# Safety_Thermocouple_Interface_-_IO.net
KiCad netlist of a schematic drawn in Altium Designer
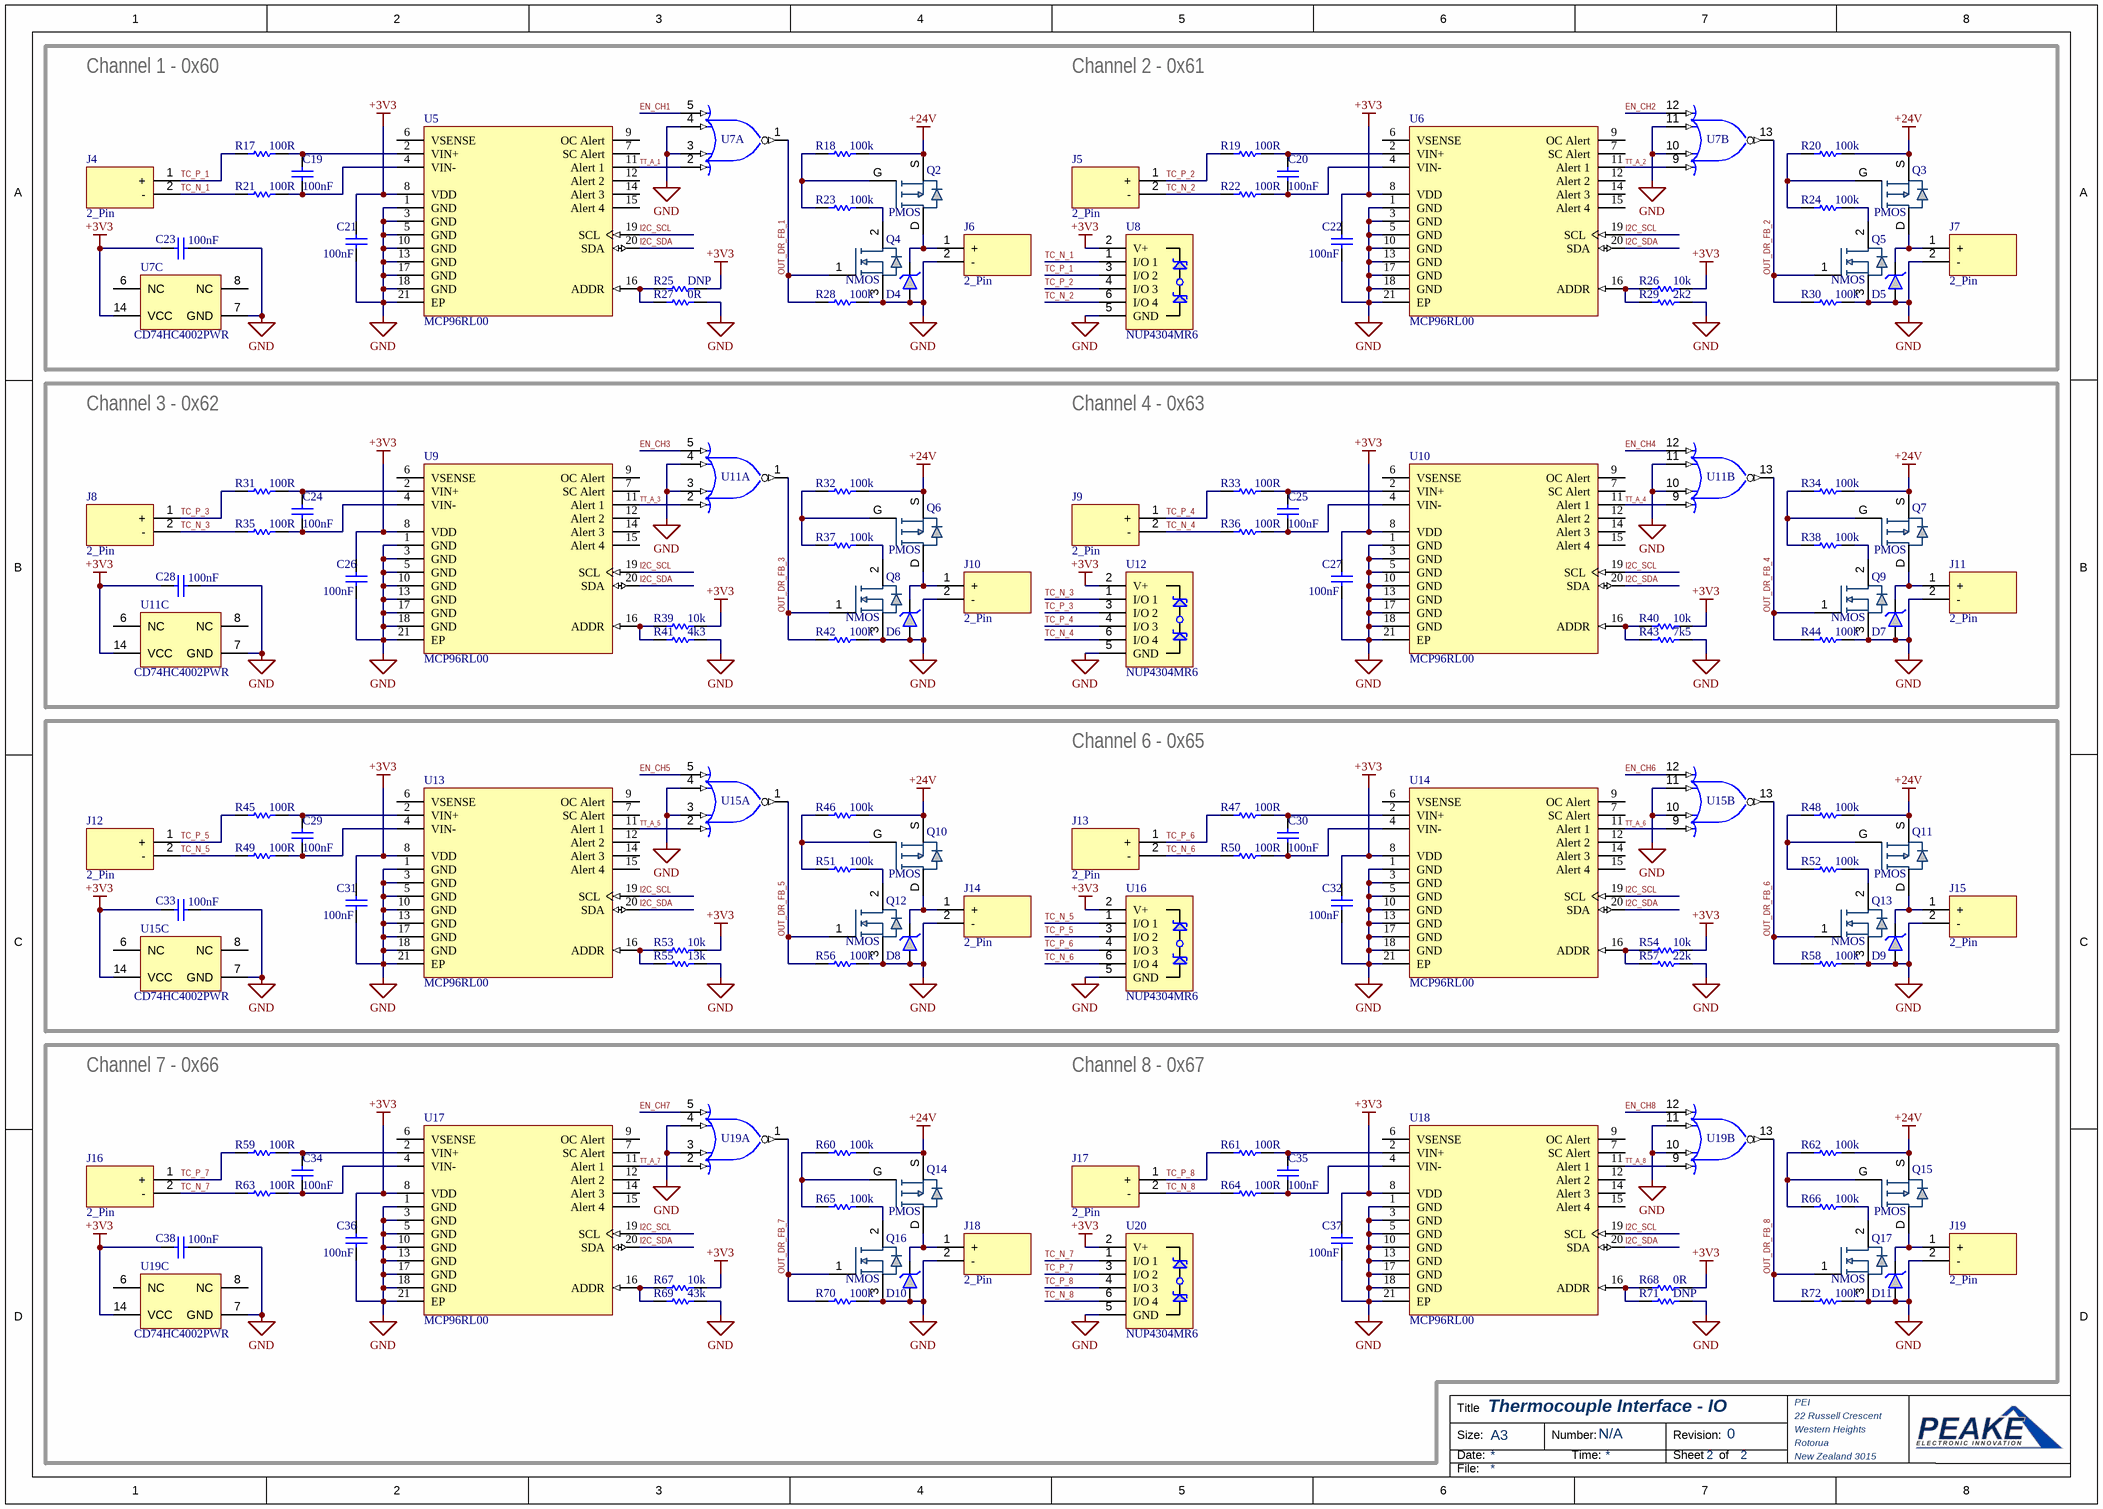
[diagram p0: Safety Thermocouple Interface - IO.SchDoc]

(export (version "E")
  (design (tool "Eeschema 10.0.6"))
  (components
    (comp (ref "C19")
      (value "100nF")
      (footprint "0603_CAP")
      (description "SMD Capacitor")
      (fields (field (name "Comment") "Capacitor"))
      (libsource (lib "Scion Research") (part "CMP-019-00005-2"))
    )
    (comp (ref "C20")
      (value "100nF")
      (footprint "0603_CAP")
      (description "SMD Capacitor")
      (fields (field (name "Comment") "Capacitor"))
      (libsource (lib "Scion Research") (part "CMP-019-00005-2"))
    )
    (comp (ref "C21")
      (value "100nF")
      (footprint "0603_CAP")
      (description "SMD Capacitor")
      (fields (field (name "Comment") "Capacitor"))
      (libsource (lib "Scion Research") (part "CMP-019-00005-2"))
    )
    (comp (ref "C22")
      (value "100nF")
      (footprint "0603_CAP")
      (description "SMD Capacitor")
      (fields (field (name "Comment") "Capacitor"))
      (libsource (lib "Scion Research") (part "CMP-019-00005-2"))
    )
    (comp (ref "C23")
      (value "100nF")
      (footprint "0603_CAP")
      (description "SMD Capacitor")
      (fields (field (name "Comment") "Capacitor"))
      (libsource (lib "Scion Research") (part "CMP-019-00005-2"))
    )
    (comp (ref "C24")
      (value "100nF")
      (footprint "0603_CAP")
      (description "SMD Capacitor")
      (fields (field (name "Comment") "Capacitor"))
      (libsource (lib "Scion Research") (part "CMP-019-00005-2"))
    )
    (comp (ref "C25")
      (value "100nF")
      (footprint "0603_CAP")
      (description "SMD Capacitor")
      (fields (field (name "Comment") "Capacitor"))
      (libsource (lib "Scion Research") (part "CMP-019-00005-2"))
    )
    (comp (ref "C26")
      (value "100nF")
      (footprint "0603_CAP")
      (description "SMD Capacitor")
      (fields (field (name "Comment") "Capacitor"))
      (libsource (lib "Scion Research") (part "CMP-019-00005-2"))
    )
    (comp (ref "C27")
      (value "100nF")
      (footprint "0603_CAP")
      (description "SMD Capacitor")
      (fields (field (name "Comment") "Capacitor"))
      (libsource (lib "Scion Research") (part "CMP-019-00005-2"))
    )
    (comp (ref "C28")
      (value "100nF")
      (footprint "0603_CAP")
      (description "SMD Capacitor")
      (fields (field (name "Comment") "Capacitor"))
      (libsource (lib "Scion Research") (part "CMP-019-00005-2"))
    )
    (comp (ref "C29")
      (value "100nF")
      (footprint "0603_CAP")
      (description "SMD Capacitor")
      (fields (field (name "Comment") "Capacitor"))
      (libsource (lib "Scion Research") (part "CMP-019-00005-2"))
    )
    (comp (ref "C30")
      (value "100nF")
      (footprint "0603_CAP")
      (description "SMD Capacitor")
      (fields (field (name "Comment") "Capacitor"))
      (libsource (lib "Scion Research") (part "CMP-019-00005-2"))
    )
    (comp (ref "C31")
      (value "100nF")
      (footprint "0603_CAP")
      (description "SMD Capacitor")
      (fields (field (name "Comment") "Capacitor"))
      (libsource (lib "Scion Research") (part "CMP-019-00005-2"))
    )
    (comp (ref "C32")
      (value "100nF")
      (footprint "0603_CAP")
      (description "SMD Capacitor")
      (fields (field (name "Comment") "Capacitor"))
      (libsource (lib "Scion Research") (part "CMP-019-00005-2"))
    )
    (comp (ref "C33")
      (value "100nF")
      (footprint "0603_CAP")
      (description "SMD Capacitor")
      (fields (field (name "Comment") "Capacitor"))
      (libsource (lib "Scion Research") (part "CMP-019-00005-2"))
    )
    (comp (ref "C34")
      (value "100nF")
      (footprint "0603_CAP")
      (description "SMD Capacitor")
      (fields (field (name "Comment") "Capacitor"))
      (libsource (lib "Scion Research") (part "CMP-019-00005-2"))
    )
    (comp (ref "C35")
      (value "100nF")
      (footprint "0603_CAP")
      (description "SMD Capacitor")
      (fields (field (name "Comment") "Capacitor"))
      (libsource (lib "Scion Research") (part "CMP-019-00005-2"))
    )
    (comp (ref "C36")
      (value "100nF")
      (footprint "0603_CAP")
      (description "SMD Capacitor")
      (fields (field (name "Comment") "Capacitor"))
      (libsource (lib "Scion Research") (part "CMP-019-00005-2"))
    )
    (comp (ref "C37")
      (value "100nF")
      (footprint "0603_CAP")
      (description "SMD Capacitor")
      (fields (field (name "Comment") "Capacitor"))
      (libsource (lib "Scion Research") (part "CMP-019-00005-2"))
    )
    (comp (ref "C38")
      (value "100nF")
      (footprint "0603_CAP")
      (description "SMD Capacitor")
      (fields (field (name "Comment") "Capacitor"))
      (libsource (lib "Scion Research") (part "CMP-019-00005-2"))
    )
    (comp (ref "D4")
      (value "Transil")
      (footprint "SMBJ")
      (description "Transient Voltage Suppressor")
      (libsource (lib "Scion Research") (part "CMP-004-0042-1"))
    )
    (comp (ref "D5")
      (value "Transil")
      (footprint "SMBJ")
      (description "Transient Voltage Suppressor")
      (libsource (lib "Scion Research") (part "CMP-004-0042-1"))
    )
    (comp (ref "D6")
      (value "Transil")
      (footprint "SMBJ")
      (description "Transient Voltage Suppressor")
      (libsource (lib "Scion Research") (part "CMP-004-0042-1"))
    )
    (comp (ref "D7")
      (value "Transil")
      (footprint "SMBJ")
      (description "Transient Voltage Suppressor")
      (libsource (lib "Scion Research") (part "CMP-004-0042-1"))
    )
    (comp (ref "D8")
      (value "Transil")
      (footprint "SMBJ")
      (description "Transient Voltage Suppressor")
      (libsource (lib "Scion Research") (part "CMP-004-0042-1"))
    )
    (comp (ref "D9")
      (value "Transil")
      (footprint "SMBJ")
      (description "Transient Voltage Suppressor")
      (libsource (lib "Scion Research") (part "CMP-004-0042-1"))
    )
    (comp (ref "D10")
      (value "Transil")
      (footprint "SMBJ")
      (description "Transient Voltage Suppressor")
      (libsource (lib "Scion Research") (part "CMP-004-0042-1"))
    )
    (comp (ref "D11")
      (value "Transil")
      (footprint "SMBJ")
      (description "Transient Voltage Suppressor")
      (libsource (lib "Scion Research") (part "CMP-004-0042-1"))
    )
    (comp (ref "J4")
      (value "2_Pin")
      (footprint "2_Pin DB2EVC-3.81-2P-GN")
      (description "2 Pin Connector")
      (libsource (lib "") (part "CMP-002-00074-8_1"))
    )
    (comp (ref "J5")
      (value "2_Pin")
      (footprint "2_Pin DB2EVC-3.81-2P-GN")
      (description "2 Pin Connector")
      (libsource (lib "") (part "CMP-002-00074-8_1"))
    )
    (comp (ref "J6")
      (value "2_Pin")
      (footprint "2_Pin DB2EVC-3.81-2P-GN")
      (description "2 Pin Connector")
      (libsource (lib "Scion Research") (part "CMP-002-00074-8"))
    )
    (comp (ref "J7")
      (value "2_Pin")
      (footprint "2_Pin DB2EVC-3.81-2P-GN")
      (description "2 Pin Connector")
      (libsource (lib "Scion Research") (part "CMP-002-00074-8"))
    )
    (comp (ref "J8")
      (value "2_Pin")
      (footprint "2_Pin DB2EVC-3.81-2P-GN")
      (description "2 Pin Connector")
      (libsource (lib "") (part "CMP-002-00074-8_1"))
    )
    (comp (ref "J9")
      (value "2_Pin")
      (footprint "2_Pin DB2EVC-3.81-2P-GN")
      (description "2 Pin Connector")
      (libsource (lib "") (part "CMP-002-00074-8_1"))
    )
    (comp (ref "J10")
      (value "2_Pin")
      (footprint "2_Pin DB2EVC-3.81-2P-GN")
      (description "2 Pin Connector")
      (libsource (lib "Scion Research") (part "CMP-002-00074-8"))
    )
    (comp (ref "J11")
      (value "2_Pin")
      (footprint "2_Pin DB2EVC-3.81-2P-GN")
      (description "2 Pin Connector")
      (libsource (lib "Scion Research") (part "CMP-002-00074-8"))
    )
    (comp (ref "J12")
      (value "2_Pin")
      (footprint "2_Pin DB2EVC-3.81-2P-GN")
      (description "2 Pin Connector")
      (libsource (lib "") (part "CMP-002-00074-8_1"))
    )
    (comp (ref "J13")
      (value "2_Pin")
      (footprint "2_Pin DB2EVC-3.81-2P-GN")
      (description "2 Pin Connector")
      (libsource (lib "") (part "CMP-002-00074-8_1"))
    )
    (comp (ref "J14")
      (value "2_Pin")
      (footprint "2_Pin DB2EVC-3.81-2P-GN")
      (description "2 Pin Connector")
      (libsource (lib "Scion Research") (part "CMP-002-00074-8"))
    )
    (comp (ref "J15")
      (value "2_Pin")
      (footprint "2_Pin DB2EVC-3.81-2P-GN")
      (description "2 Pin Connector")
      (libsource (lib "Scion Research") (part "CMP-002-00074-8"))
    )
    (comp (ref "J16")
      (value "2_Pin")
      (footprint "2_Pin DB2EVC-3.81-2P-GN")
      (description "2 Pin Connector")
      (libsource (lib "") (part "CMP-002-00074-8_1"))
    )
    (comp (ref "J17")
      (value "2_Pin")
      (footprint "2_Pin DB2EVC-3.81-2P-GN")
      (description "2 Pin Connector")
      (libsource (lib "") (part "CMP-002-00074-8_1"))
    )
    (comp (ref "J18")
      (value "2_Pin")
      (footprint "2_Pin DB2EVC-3.81-2P-GN")
      (description "2 Pin Connector")
      (libsource (lib "Scion Research") (part "CMP-002-00074-8"))
    )
    (comp (ref "J19")
      (value "2_Pin")
      (footprint "2_Pin DB2EVC-3.81-2P-GN")
      (description "2 Pin Connector")
      (libsource (lib "Scion Research") (part "CMP-002-00074-8"))
    )
    (comp (ref "Q2")
      (value "PMOS")
      (footprint "PowerDI 5060-8")
      (description "P Channel MOSFET")
      (libsource (lib "Scion Research") (part "CMP-004-0035-2"))
    )
    (comp (ref "Q3")
      (value "PMOS")
      (footprint "PowerDI 5060-8")
      (description "P Channel MOSFET")
      (libsource (lib "Scion Research") (part "CMP-004-0035-2"))
    )
    (comp (ref "Q4")
      (value "NMOS")
      (footprint "SOT-23")
      (description "N Channel MOSFET")
      (libsource (lib "Scion Research") (part "CMP-004-0025-1"))
    )
    (comp (ref "Q5")
      (value "NMOS")
      (footprint "SOT-23")
      (description "N Channel MOSFET")
      (libsource (lib "Scion Research") (part "CMP-004-0025-1"))
    )
    (comp (ref "Q6")
      (value "PMOS")
      (footprint "PowerDI 5060-8")
      (description "P Channel MOSFET")
      (libsource (lib "Scion Research") (part "CMP-004-0035-2"))
    )
    (comp (ref "Q7")
      (value "PMOS")
      (footprint "PowerDI 5060-8")
      (description "P Channel MOSFET")
      (libsource (lib "Scion Research") (part "CMP-004-0035-2"))
    )
    (comp (ref "Q8")
      (value "NMOS")
      (footprint "SOT-23")
      (description "N Channel MOSFET")
      (libsource (lib "Scion Research") (part "CMP-004-0025-1"))
    )
    (comp (ref "Q9")
      (value "NMOS")
      (footprint "SOT-23")
      (description "N Channel MOSFET")
      (libsource (lib "Scion Research") (part "CMP-004-0025-1"))
    )
    (comp (ref "Q10")
      (value "PMOS")
      (footprint "PowerDI 5060-8")
      (description "P Channel MOSFET")
      (libsource (lib "Scion Research") (part "CMP-004-0035-2"))
    )
    (comp (ref "Q11")
      (value "PMOS")
      (footprint "PowerDI 5060-8")
      (description "P Channel MOSFET")
      (libsource (lib "Scion Research") (part "CMP-004-0035-2"))
    )
    (comp (ref "Q12")
      (value "NMOS")
      (footprint "SOT-23")
      (description "N Channel MOSFET")
      (libsource (lib "Scion Research") (part "CMP-004-0025-1"))
    )
    (comp (ref "Q13")
      (value "NMOS")
      (footprint "SOT-23")
      (description "N Channel MOSFET")
      (libsource (lib "Scion Research") (part "CMP-004-0025-1"))
    )
    (comp (ref "Q14")
      (value "PMOS")
      (footprint "PowerDI 5060-8")
      (description "P Channel MOSFET")
      (libsource (lib "Scion Research") (part "CMP-004-0035-2"))
    )
    (comp (ref "Q15")
      (value "PMOS")
      (footprint "PowerDI 5060-8")
      (description "P Channel MOSFET")
      (libsource (lib "Scion Research") (part "CMP-004-0035-2"))
    )
    (comp (ref "Q16")
      (value "NMOS")
      (footprint "SOT-23")
      (description "N Channel MOSFET")
      (libsource (lib "Scion Research") (part "CMP-004-0025-1"))
    )
    (comp (ref "Q17")
      (value "NMOS")
      (footprint "SOT-23")
      (description "N Channel MOSFET")
      (libsource (lib "Scion Research") (part "CMP-004-0025-1"))
    )
    (comp (ref "R17")
      (value "100R")
      (footprint "0603_RES")
      (description "SMD Resistor")
      (fields (field (name "Comment") "Resistor"))
      (libsource (lib "Scion Research") (part "Resistor SMD"))
    )
    (comp (ref "R18")
      (value "100k")
      (footprint "0603_RES")
      (description "SMD Resistor")
      (fields (field (name "Comment") "Resistor"))
      (libsource (lib "Scion Research") (part "Resistor SMD"))
    )
    (comp (ref "R19")
      (value "100R")
      (footprint "0603_RES")
      (description "SMD Resistor")
      (fields (field (name "Comment") "Resistor"))
      (libsource (lib "Scion Research") (part "Resistor SMD"))
    )
    (comp (ref "R20")
      (value "100k")
      (footprint "0603_RES")
      (description "SMD Resistor")
      (fields (field (name "Comment") "Resistor"))
      (libsource (lib "Scion Research") (part "Resistor SMD"))
    )
    (comp (ref "R21")
      (value "100R")
      (footprint "0603_RES")
      (description "SMD Resistor")
      (fields (field (name "Comment") "Resistor"))
      (libsource (lib "Scion Research") (part "Resistor SMD"))
    )
    (comp (ref "R22")
      (value "100R")
      (footprint "0603_RES")
      (description "SMD Resistor")
      (fields (field (name "Comment") "Resistor"))
      (libsource (lib "Scion Research") (part "Resistor SMD"))
    )
    (comp (ref "R23")
      (value "100k")
      (footprint "0603_RES")
      (description "SMD Resistor")
      (fields (field (name "Comment") "Resistor"))
      (libsource (lib "Scion Research") (part "Resistor SMD"))
    )
    (comp (ref "R24")
      (value "100k")
      (footprint "0603_RES")
      (description "SMD Resistor")
      (fields (field (name "Comment") "Resistor"))
      (libsource (lib "Scion Research") (part "Resistor SMD"))
    )
    (comp (ref "R25")
      (value "DNP")
      (footprint "0603_RES")
      (description "SMD Resistor")
      (fields (field (name "Comment") "Resistor"))
      (libsource (lib "Scion Research") (part "Resistor SMD"))
    )
    (comp (ref "R26")
      (value "10k")
      (footprint "0603_RES")
      (description "SMD Resistor")
      (fields (field (name "Comment") "Resistor"))
      (libsource (lib "Scion Research") (part "Resistor SMD"))
    )
    (comp (ref "R27")
      (value "0R")
      (footprint "0603_RES")
      (description "SMD Resistor")
      (fields (field (name "Comment") "Resistor"))
      (libsource (lib "Scion Research") (part "Resistor SMD"))
    )
    (comp (ref "R28")
      (value "100k")
      (footprint "0603_RES")
      (description "SMD Resistor")
      (fields (field (name "Comment") "Resistor"))
      (libsource (lib "Scion Research") (part "Resistor SMD"))
    )
    (comp (ref "R29")
      (value "2k2")
      (footprint "0603_RES")
      (description "SMD Resistor")
      (fields (field (name "Comment") "Resistor"))
      (libsource (lib "Scion Research") (part "Resistor SMD"))
    )
    (comp (ref "R30")
      (value "100k")
      (footprint "0603_RES")
      (description "SMD Resistor")
      (fields (field (name "Comment") "Resistor"))
      (libsource (lib "Scion Research") (part "Resistor SMD"))
    )
    (comp (ref "R31")
      (value "100R")
      (footprint "0603_RES")
      (description "SMD Resistor")
      (fields (field (name "Comment") "Resistor"))
      (libsource (lib "Scion Research") (part "Resistor SMD"))
    )
    (comp (ref "R32")
      (value "100k")
      (footprint "0603_RES")
      (description "SMD Resistor")
      (fields (field (name "Comment") "Resistor"))
      (libsource (lib "Scion Research") (part "Resistor SMD"))
    )
    (comp (ref "R33")
      (value "100R")
      (footprint "0603_RES")
      (description "SMD Resistor")
      (fields (field (name "Comment") "Resistor"))
      (libsource (lib "Scion Research") (part "Resistor SMD"))
    )
    (comp (ref "R34")
      (value "100k")
      (footprint "0603_RES")
      (description "SMD Resistor")
      (fields (field (name "Comment") "Resistor"))
      (libsource (lib "Scion Research") (part "Resistor SMD"))
    )
    (comp (ref "R35")
      (value "100R")
      (footprint "0603_RES")
      (description "SMD Resistor")
      (fields (field (name "Comment") "Resistor"))
      (libsource (lib "Scion Research") (part "Resistor SMD"))
    )
    (comp (ref "R36")
      (value "100R")
      (footprint "0603_RES")
      (description "SMD Resistor")
      (fields (field (name "Comment") "Resistor"))
      (libsource (lib "Scion Research") (part "Resistor SMD"))
    )
    (comp (ref "R37")
      (value "100k")
      (footprint "0603_RES")
      (description "SMD Resistor")
      (fields (field (name "Comment") "Resistor"))
      (libsource (lib "Scion Research") (part "Resistor SMD"))
    )
    (comp (ref "R38")
      (value "100k")
      (footprint "0603_RES")
      (description "SMD Resistor")
      (fields (field (name "Comment") "Resistor"))
      (libsource (lib "Scion Research") (part "Resistor SMD"))
    )
    (comp (ref "R39")
      (value "10k")
      (footprint "0603_RES")
      (description "SMD Resistor")
      (fields (field (name "Comment") "Resistor"))
      (libsource (lib "Scion Research") (part "Resistor SMD"))
    )
    (comp (ref "R40")
      (value "10k")
      (footprint "0603_RES")
      (description "SMD Resistor")
      (fields (field (name "Comment") "Resistor"))
      (libsource (lib "Scion Research") (part "Resistor SMD"))
    )
    (comp (ref "R41")
      (value "4k3")
      (footprint "0603_RES")
      (description "SMD Resistor")
      (fields (field (name "Comment") "Resistor"))
      (libsource (lib "Scion Research") (part "Resistor SMD"))
    )
    (comp (ref "R42")
      (value "100k")
      (footprint "0603_RES")
      (description "SMD Resistor")
      (fields (field (name "Comment") "Resistor"))
      (libsource (lib "Scion Research") (part "Resistor SMD"))
    )
    (comp (ref "R43")
      (value "7k5")
      (footprint "0603_RES")
      (description "SMD Resistor")
      (fields (field (name "Comment") "Resistor"))
      (libsource (lib "Scion Research") (part "Resistor SMD"))
    )
    (comp (ref "R44")
      (value "100k")
      (footprint "0603_RES")
      (description "SMD Resistor")
      (fields (field (name "Comment") "Resistor"))
      (libsource (lib "Scion Research") (part "Resistor SMD"))
    )
    (comp (ref "R45")
      (value "100R")
      (footprint "0603_RES")
      (description "SMD Resistor")
      (fields (field (name "Comment") "Resistor"))
      (libsource (lib "Scion Research") (part "Resistor SMD"))
    )
    (comp (ref "R46")
      (value "100k")
      (footprint "0603_RES")
      (description "SMD Resistor")
      (fields (field (name "Comment") "Resistor"))
      (libsource (lib "Scion Research") (part "Resistor SMD"))
    )
    (comp (ref "R47")
      (value "100R")
      (footprint "0603_RES")
      (description "SMD Resistor")
      (fields (field (name "Comment") "Resistor"))
      (libsource (lib "Scion Research") (part "Resistor SMD"))
    )
    (comp (ref "R48")
      (value "100k")
      (footprint "0603_RES")
      (description "SMD Resistor")
      (fields (field (name "Comment") "Resistor"))
      (libsource (lib "Scion Research") (part "Resistor SMD"))
    )
    (comp (ref "R49")
      (value "100R")
      (footprint "0603_RES")
      (description "SMD Resistor")
      (fields (field (name "Comment") "Resistor"))
      (libsource (lib "Scion Research") (part "Resistor SMD"))
    )
    (comp (ref "R50")
      (value "100R")
      (footprint "0603_RES")
      (description "SMD Resistor")
      (fields (field (name "Comment") "Resistor"))
      (libsource (lib "Scion Research") (part "Resistor SMD"))
    )
    (comp (ref "R51")
      (value "100k")
      (footprint "0603_RES")
      (description "SMD Resistor")
      (fields (field (name "Comment") "Resistor"))
      (libsource (lib "Scion Research") (part "Resistor SMD"))
    )
    (comp (ref "R52")
      (value "100k")
      (footprint "0603_RES")
      (description "SMD Resistor")
      (fields (field (name "Comment") "Resistor"))
      (libsource (lib "Scion Research") (part "Resistor SMD"))
    )
    (comp (ref "R53")
      (value "10k")
      (footprint "0603_RES")
      (description "SMD Resistor")
      (fields (field (name "Comment") "Resistor"))
      (libsource (lib "Scion Research") (part "Resistor SMD"))
    )
    (comp (ref "R54")
      (value "10k")
      (footprint "0603_RES")
      (description "SMD Resistor")
      (fields (field (name "Comment") "Resistor"))
      (libsource (lib "Scion Research") (part "Resistor SMD"))
    )
    (comp (ref "R55")
      (value "13k")
      (footprint "0603_RES")
      (description "SMD Resistor")
      (fields (field (name "Comment") "Resistor"))
      (libsource (lib "Scion Research") (part "Resistor SMD"))
    )
    (comp (ref "R56")
      (value "100k")
      (footprint "0603_RES")
      (description "SMD Resistor")
      (fields (field (name "Comment") "Resistor"))
      (libsource (lib "Scion Research") (part "Resistor SMD"))
    )
    (comp (ref "R57")
      (value "22k")
      (footprint "0603_RES")
      (description "SMD Resistor")
      (fields (field (name "Comment") "Resistor"))
      (libsource (lib "Scion Research") (part "Resistor SMD"))
    )
    (comp (ref "R58")
      (value "100k")
      (footprint "0603_RES")
      (description "SMD Resistor")
      (fields (field (name "Comment") "Resistor"))
      (libsource (lib "Scion Research") (part "Resistor SMD"))
    )
    (comp (ref "R59")
      (value "100R")
      (footprint "0603_RES")
      (description "SMD Resistor")
      (fields (field (name "Comment") "Resistor"))
      (libsource (lib "Scion Research") (part "Resistor SMD"))
    )
    (comp (ref "R60")
      (value "100k")
      (footprint "0603_RES")
      (description "SMD Resistor")
      (fields (field (name "Comment") "Resistor"))
      (libsource (lib "Scion Research") (part "Resistor SMD"))
    )
    (comp (ref "R61")
      (value "100R")
      (footprint "0603_RES")
      (description "SMD Resistor")
      (fields (field (name "Comment") "Resistor"))
      (libsource (lib "Scion Research") (part "Resistor SMD"))
    )
    (comp (ref "R62")
      (value "100k")
      (footprint "0603_RES")
      (description "SMD Resistor")
      (fields (field (name "Comment") "Resistor"))
      (libsource (lib "Scion Research") (part "Resistor SMD"))
    )
    (comp (ref "R63")
      (value "100R")
      (footprint "0603_RES")
      (description "SMD Resistor")
      (fields (field (name "Comment") "Resistor"))
      (libsource (lib "Scion Research") (part "Resistor SMD"))
    )
    (comp (ref "R64")
      (value "100R")
      (footprint "0603_RES")
      (description "SMD Resistor")
      (fields (field (name "Comment") "Resistor"))
      (libsource (lib "Scion Research") (part "Resistor SMD"))
    )
    (comp (ref "R65")
      (value "100k")
      (footprint "0603_RES")
      (description "SMD Resistor")
      (fields (field (name "Comment") "Resistor"))
      (libsource (lib "Scion Research") (part "Resistor SMD"))
    )
    (comp (ref "R66")
      (value "100k")
      (footprint "0603_RES")
      (description "SMD Resistor")
      (fields (field (name "Comment") "Resistor"))
      (libsource (lib "Scion Research") (part "Resistor SMD"))
    )
    (comp (ref "R67")
      (value "10k")
      (footprint "0603_RES")
      (description "SMD Resistor")
      (fields (field (name "Comment") "Resistor"))
      (libsource (lib "Scion Research") (part "Resistor SMD"))
    )
    (comp (ref "R68")
      (value "0R")
      (footprint "0603_RES")
      (description "SMD Resistor")
      (fields (field (name "Comment") "Resistor"))
      (libsource (lib "Scion Research") (part "Resistor SMD"))
    )
    (comp (ref "R69")
      (value "43k")
      (footprint "0603_RES")
      (description "SMD Resistor")
      (fields (field (name "Comment") "Resistor"))
      (libsource (lib "Scion Research") (part "Resistor SMD"))
    )
    (comp (ref "R70")
      (value "100k")
      (footprint "0603_RES")
      (description "SMD Resistor")
      (fields (field (name "Comment") "Resistor"))
      (libsource (lib "Scion Research") (part "Resistor SMD"))
    )
    (comp (ref "R71")
      (value "DNP")
      (footprint "0603_RES")
      (description "SMD Resistor")
      (fields (field (name "Comment") "Resistor"))
      (libsource (lib "Scion Research") (part "Resistor SMD"))
    )
    (comp (ref "R72")
      (value "100k")
      (footprint "0603_RES")
      (description "SMD Resistor")
      (fields (field (name "Comment") "Resistor"))
      (libsource (lib "Scion Research") (part "Resistor SMD"))
    )
    (comp (ref "U5")
      (value "MCP96RL00")
      (footprint "FP-C04-186-IPC_B")
      (description "Analog Circuit")
      (libsource (lib "Scion Research") (part "MCP9601"))
    )
    (comp (ref "U6")
      (value "MCP96RL00")
      (footprint "FP-C04-186-IPC_B")
      (description "Analog Circuit")
      (libsource (lib "Scion Research") (part "MCP9601"))
    )
    (comp (ref "U7")
      (value "CD74HC4002PWR")
      (footprint "PW0014A_N")
      (description "NOR Gate, HC Series, 2-Func, 4-Input, CMOS, PDSO14")
      (libsource (lib "") (part "TI-CD_SNX4HC4002-14_1"))
    )
    (comp (ref "U8")
      (value "NUP4304MR6")
      (footprint "TSOP-6")
      (description "ESD Protection Doide Array")
      (libsource (lib "Scion Research") (part "CMP-004-0028-1"))
    )
    (comp (ref "U9")
      (value "MCP96RL00")
      (footprint "FP-C04-186-IPC_B")
      (description "Analog Circuit")
      (libsource (lib "Scion Research") (part "MCP9601"))
    )
    (comp (ref "U10")
      (value "MCP96RL00")
      (footprint "FP-C04-186-IPC_B")
      (description "Analog Circuit")
      (libsource (lib "Scion Research") (part "MCP9601"))
    )
    (comp (ref "U11")
      (value "CD74HC4002PWR")
      (footprint "PW0014A_N")
      (description "NOR Gate, HC Series, 2-Func, 4-Input, CMOS, PDSO14")
      (libsource (lib "") (part "TI-CD_SNX4HC4002-14_1"))
    )
    (comp (ref "U12")
      (value "NUP4304MR6")
      (footprint "TSOP-6")
      (description "ESD Protection Doide Array")
      (libsource (lib "Scion Research") (part "CMP-004-0028-1"))
    )
    (comp (ref "U13")
      (value "MCP96RL00")
      (footprint "FP-C04-186-IPC_B")
      (description "Analog Circuit")
      (libsource (lib "Scion Research") (part "MCP9601"))
    )
    (comp (ref "U14")
      (value "MCP96RL00")
      (footprint "FP-C04-186-IPC_B")
      (description "Analog Circuit")
      (libsource (lib "Scion Research") (part "MCP9601"))
    )
    (comp (ref "U15")
      (value "CD74HC4002PWR")
      (footprint "PW0014A_N")
      (description "NOR Gate, HC Series, 2-Func, 4-Input, CMOS, PDSO14")
      (libsource (lib "Scion Research") (part "TI-CD_SNX4HC4002-14"))
    )
    (comp (ref "U16")
      (value "NUP4304MR6")
      (footprint "TSOP-6")
      (description "ESD Protection Doide Array")
      (libsource (lib "Scion Research") (part "CMP-004-0028-1"))
    )
    (comp (ref "U17")
      (value "MCP96RL00")
      (footprint "FP-C04-186-IPC_B")
      (description "Analog Circuit")
      (libsource (lib "Scion Research") (part "MCP9601"))
    )
    (comp (ref "U18")
      (value "MCP96RL00")
      (footprint "FP-C04-186-IPC_B")
      (description "Analog Circuit")
      (libsource (lib "Scion Research") (part "MCP9601"))
    )
    (comp (ref "U19")
      (value "CD74HC4002PWR")
      (footprint "PW0014A_N")
      (description "NOR Gate, HC Series, 2-Func, 4-Input, CMOS, PDSO14")
      (libsource (lib "Scion Research") (part "TI-CD_SNX4HC4002-14"))
    )
    (comp (ref "U20")
      (value "NUP4304MR6")
      (footprint "TSOP-6")
      (description "ESD Protection Doide Array")
      (libsource (lib "Scion Research") (part "CMP-004-0028-1"))
    )
  )
  (nets
    (net (code "1") (name "+3V3") (class "Default")
      (node (ref "C21") (pin "2") (pinfunction "2_2") (pintype "passive"))
      (node (ref "C22") (pin "2") (pinfunction "2_2") (pintype "passive"))
      (node (ref "C23") (pin "2") (pinfunction "2_2") (pintype "passive"))
      (node (ref "C26") (pin "2") (pinfunction "2_2") (pintype "passive"))
      (node (ref "C27") (pin "2") (pinfunction "2_2") (pintype "passive"))
      (node (ref "C28") (pin "2") (pinfunction "2_2") (pintype "passive"))
      (node (ref "C31") (pin "2") (pinfunction "2_2") (pintype "passive"))
      (node (ref "C32") (pin "2") (pinfunction "2_2") (pintype "passive"))
      (node (ref "C33") (pin "2") (pinfunction "2_2") (pintype "passive"))
      (node (ref "C36") (pin "2") (pinfunction "2_2") (pintype "passive"))
      (node (ref "C37") (pin "2") (pinfunction "2_2") (pintype "passive"))
      (node (ref "C38") (pin "2") (pinfunction "2_2") (pintype "passive"))
      (node (ref "R25") (pin "1") (pinfunction "1_1") (pintype "passive"))
      (node (ref "R26") (pin "1") (pinfunction "1_1") (pintype "passive"))
      (node (ref "R39") (pin "1") (pinfunction "1_1") (pintype "passive"))
      (node (ref "R40") (pin "1") (pinfunction "1_1") (pintype "passive"))
      (node (ref "R53") (pin "1") (pinfunction "1_1") (pintype "passive"))
      (node (ref "R54") (pin "1") (pinfunction "1_1") (pintype "passive"))
      (node (ref "R67") (pin "1") (pinfunction "1_1") (pintype "passive"))
      (node (ref "R68") (pin "1") (pinfunction "1_1") (pintype "passive"))
      (node (ref "U10") (pin "8") (pinfunction "VDD_8") (pintype "power_in"))
      (node (ref "U11") (pin "14") (pinfunction "VCC_14") (pintype "power_in"))
      (node (ref "U12") (pin "2") (pinfunction "V+_2") (pintype "power_in"))
      (node (ref "U13") (pin "8") (pinfunction "VDD_8") (pintype "power_in"))
      (node (ref "U14") (pin "8") (pinfunction "VDD_8") (pintype "power_in"))
      (node (ref "U15") (pin "14") (pinfunction "VCC_14") (pintype "power_in"))
      (node (ref "U16") (pin "2") (pinfunction "V+_2") (pintype "power_in"))
      (node (ref "U17") (pin "8") (pinfunction "VDD_8") (pintype "power_in"))
      (node (ref "U18") (pin "8") (pinfunction "VDD_8") (pintype "power_in"))
      (node (ref "U19") (pin "14") (pinfunction "VCC_14") (pintype "power_in"))
      (node (ref "U20") (pin "2") (pinfunction "V+_2") (pintype "power_in"))
      (node (ref "U5") (pin "8") (pinfunction "VDD_8") (pintype "power_in"))
      (node (ref "U6") (pin "8") (pinfunction "VDD_8") (pintype "power_in"))
      (node (ref "U7") (pin "14") (pinfunction "VCC_14") (pintype "power_in"))
      (node (ref "U8") (pin "2") (pinfunction "V+_2") (pintype "power_in"))
      (node (ref "U9") (pin "8") (pinfunction "VDD_8") (pintype "power_in"))
    )
    (net (code "2") (name "+24V") (class "Default")
      (node (ref "Q10") (pin "S") (pinfunction "S_S") (pintype "passive"))
      (node (ref "Q11") (pin "S") (pinfunction "S_S") (pintype "passive"))
      (node (ref "Q14") (pin "S") (pinfunction "S_S") (pintype "passive"))
      (node (ref "Q15") (pin "S") (pinfunction "S_S") (pintype "passive"))
      (node (ref "Q2") (pin "S") (pinfunction "S_S") (pintype "passive"))
      (node (ref "Q3") (pin "S") (pinfunction "S_S") (pintype "passive"))
      (node (ref "Q6") (pin "S") (pinfunction "S_S") (pintype "passive"))
      (node (ref "Q7") (pin "S") (pinfunction "S_S") (pintype "passive"))
      (node (ref "R18") (pin "1") (pinfunction "1_1") (pintype "passive"))
      (node (ref "R20") (pin "1") (pinfunction "1_1") (pintype "passive"))
      (node (ref "R32") (pin "1") (pinfunction "1_1") (pintype "passive"))
      (node (ref "R34") (pin "1") (pinfunction "1_1") (pintype "passive"))
      (node (ref "R46") (pin "1") (pinfunction "1_1") (pintype "passive"))
      (node (ref "R48") (pin "1") (pinfunction "1_1") (pintype "passive"))
      (node (ref "R60") (pin "1") (pinfunction "1_1") (pintype "passive"))
      (node (ref "R62") (pin "1") (pinfunction "1_1") (pintype "passive"))
    )
    (net (code "3") (name "/EN_CH1") (class "Default")
      (node (ref "U7") (pin "5") (pinfunction "1D_5") (pintype "input"))
    )
    (net (code "4") (name "/EN_CH2") (class "Default")
      (node (ref "U7") (pin "12") (pinfunction "2D_12") (pintype "input"))
    )
    (net (code "5") (name "/EN_CH3") (class "Default")
      (node (ref "U11") (pin "5") (pinfunction "1D_5") (pintype "input"))
    )
    (net (code "6") (name "/EN_CH4") (class "Default")
      (node (ref "U11") (pin "12") (pinfunction "2D_12") (pintype "input"))
    )
    (net (code "7") (name "/EN_CH5") (class "Default")
      (node (ref "U15") (pin "5") (pinfunction "1D_5") (pintype "input"))
    )
    (net (code "8") (name "/EN_CH6") (class "Default")
      (node (ref "U15") (pin "12") (pinfunction "2D_12") (pintype "input"))
    )
    (net (code "9") (name "/EN_CH7") (class "Default")
      (node (ref "U19") (pin "5") (pinfunction "1D_5") (pintype "input"))
    )
    (net (code "10") (name "/EN_CH8") (class "Default")
      (node (ref "U19") (pin "12") (pinfunction "2D_12") (pintype "input"))
    )
    (net (code "11") (name "/I2C_SCL") (class "Default")
      (node (ref "U10") (pin "19") (pinfunction "SCL_19") (pintype "input"))
      (node (ref "U13") (pin "19") (pinfunction "SCL_19") (pintype "input"))
      (node (ref "U14") (pin "19") (pinfunction "SCL_19") (pintype "input"))
      (node (ref "U17") (pin "19") (pinfunction "SCL_19") (pintype "input"))
      (node (ref "U18") (pin "19") (pinfunction "SCL_19") (pintype "input"))
      (node (ref "U5") (pin "19") (pinfunction "SCL_19") (pintype "input"))
      (node (ref "U6") (pin "19") (pinfunction "SCL_19") (pintype "input"))
      (node (ref "U9") (pin "19") (pinfunction "SCL_19") (pintype "input"))
    )
    (net (code "12") (name "/I2C_SDA") (class "Default")
      (node (ref "U10") (pin "20") (pinfunction "SDA_20") (pintype "bidirectional"))
      (node (ref "U13") (pin "20") (pinfunction "SDA_20") (pintype "bidirectional"))
      (node (ref "U14") (pin "20") (pinfunction "SDA_20") (pintype "bidirectional"))
      (node (ref "U17") (pin "20") (pinfunction "SDA_20") (pintype "bidirectional"))
      (node (ref "U18") (pin "20") (pinfunction "SDA_20") (pintype "bidirectional"))
      (node (ref "U5") (pin "20") (pinfunction "SDA_20") (pintype "bidirectional"))
      (node (ref "U6") (pin "20") (pinfunction "SDA_20") (pintype "bidirectional"))
      (node (ref "U9") (pin "20") (pinfunction "SDA_20") (pintype "bidirectional"))
    )
    (net (code "13") (name "/OUT_DR_FB_1") (class "Default")
      (node (ref "Q4") (pin "1") (pinfunction "G_1") (pintype "passive"))
      (node (ref "R28") (pin "2") (pinfunction "2_2") (pintype "passive"))
      (node (ref "U7") (pin "1") (pinfunction "1Y_1") (pintype "output"))
    )
    (net (code "14") (name "/OUT_DR_FB_2") (class "Default")
      (node (ref "Q5") (pin "1") (pinfunction "G_1") (pintype "passive"))
      (node (ref "R30") (pin "2") (pinfunction "2_2") (pintype "passive"))
      (node (ref "U7") (pin "13") (pinfunction "2Y_13") (pintype "output"))
    )
    (net (code "15") (name "/OUT_DR_FB_3") (class "Default")
      (node (ref "Q8") (pin "1") (pinfunction "G_1") (pintype "passive"))
      (node (ref "R42") (pin "2") (pinfunction "2_2") (pintype "passive"))
      (node (ref "U11") (pin "1") (pinfunction "1Y_1") (pintype "output"))
    )
    (net (code "16") (name "/OUT_DR_FB_4") (class "Default")
      (node (ref "Q9") (pin "1") (pinfunction "G_1") (pintype "passive"))
      (node (ref "R44") (pin "2") (pinfunction "2_2") (pintype "passive"))
      (node (ref "U11") (pin "13") (pinfunction "2Y_13") (pintype "output"))
    )
    (net (code "17") (name "/OUT_DR_FB_5") (class "Default")
      (node (ref "Q12") (pin "1") (pinfunction "G_1") (pintype "passive"))
      (node (ref "R56") (pin "2") (pinfunction "2_2") (pintype "passive"))
      (node (ref "U15") (pin "1") (pinfunction "1Y_1") (pintype "output"))
    )
    (net (code "18") (name "/OUT_DR_FB_6") (class "Default")
      (node (ref "Q13") (pin "1") (pinfunction "G_1") (pintype "passive"))
      (node (ref "R58") (pin "2") (pinfunction "2_2") (pintype "passive"))
      (node (ref "U15") (pin "13") (pinfunction "2Y_13") (pintype "output"))
    )
    (net (code "19") (name "/OUT_DR_FB_7") (class "Default")
      (node (ref "Q16") (pin "1") (pinfunction "G_1") (pintype "passive"))
      (node (ref "R70") (pin "2") (pinfunction "2_2") (pintype "passive"))
      (node (ref "U19") (pin "1") (pinfunction "1Y_1") (pintype "output"))
    )
    (net (code "20") (name "/OUT_DR_FB_8") (class "Default")
      (node (ref "Q17") (pin "1") (pinfunction "G_1") (pintype "passive"))
      (node (ref "R72") (pin "2") (pinfunction "2_2") (pintype "passive"))
      (node (ref "U19") (pin "13") (pinfunction "2Y_13") (pintype "output"))
    )
    (net (code "21") (name "/TC_N_1") (class "Default")
      (node (ref "J4") (pin "2") (pinfunction "-_2") (pintype "passive"))
      (node (ref "R21") (pin "2") (pinfunction "2_2") (pintype "passive"))
      (node (ref "U8") (pin "1") (pinfunction "I/O_1_1") (pintype "power_in"))
    )
    (net (code "22") (name "/TC_N_2") (class "Default")
      (node (ref "J5") (pin "2") (pinfunction "-_2") (pintype "passive"))
      (node (ref "R22") (pin "2") (pinfunction "2_2") (pintype "passive"))
      (node (ref "U8") (pin "6") (pinfunction "I/O_4_6") (pintype "power_in"))
    )
    (net (code "23") (name "/TC_N_3") (class "Default")
      (node (ref "J8") (pin "2") (pinfunction "-_2") (pintype "passive"))
      (node (ref "R35") (pin "2") (pinfunction "2_2") (pintype "passive"))
      (node (ref "U12") (pin "1") (pinfunction "I/O_1_1") (pintype "power_in"))
    )
    (net (code "24") (name "/TC_N_4") (class "Default")
      (node (ref "J9") (pin "2") (pinfunction "-_2") (pintype "passive"))
      (node (ref "R36") (pin "2") (pinfunction "2_2") (pintype "passive"))
      (node (ref "U12") (pin "6") (pinfunction "I/O_4_6") (pintype "power_in"))
    )
    (net (code "25") (name "/TC_N_5") (class "Default")
      (node (ref "J12") (pin "2") (pinfunction "-_2") (pintype "passive"))
      (node (ref "R49") (pin "2") (pinfunction "2_2") (pintype "passive"))
      (node (ref "U16") (pin "1") (pinfunction "I/O_1_1") (pintype "power_in"))
    )
    (net (code "26") (name "/TC_N_6") (class "Default")
      (node (ref "J13") (pin "2") (pinfunction "-_2") (pintype "passive"))
      (node (ref "R50") (pin "2") (pinfunction "2_2") (pintype "passive"))
      (node (ref "U16") (pin "6") (pinfunction "I/O_4_6") (pintype "power_in"))
    )
    (net (code "27") (name "/TC_N_7") (class "Default")
      (node (ref "J16") (pin "2") (pinfunction "-_2") (pintype "passive"))
      (node (ref "R63") (pin "2") (pinfunction "2_2") (pintype "passive"))
      (node (ref "U20") (pin "1") (pinfunction "I/O_1_1") (pintype "power_in"))
    )
    (net (code "28") (name "/TC_N_8") (class "Default")
      (node (ref "J17") (pin "2") (pinfunction "-_2") (pintype "passive"))
      (node (ref "R64") (pin "2") (pinfunction "2_2") (pintype "passive"))
      (node (ref "U20") (pin "6") (pinfunction "I/O_4_6") (pintype "power_in"))
    )
    (net (code "29") (name "/TC_P_1") (class "Default")
      (node (ref "J4") (pin "1") (pinfunction "+_1") (pintype "passive"))
      (node (ref "R17") (pin "2") (pinfunction "2_2") (pintype "passive"))
      (node (ref "U8") (pin "3") (pinfunction "I/O_2_3") (pintype "power_in"))
    )
    (net (code "30") (name "/TC_P_2") (class "Default")
      (node (ref "J5") (pin "1") (pinfunction "+_1") (pintype "passive"))
      (node (ref "R19") (pin "2") (pinfunction "2_2") (pintype "passive"))
      (node (ref "U8") (pin "4") (pinfunction "I/O_3_4") (pintype "power_in"))
    )
    (net (code "31") (name "/TC_P_3") (class "Default")
      (node (ref "J8") (pin "1") (pinfunction "+_1") (pintype "passive"))
      (node (ref "R31") (pin "2") (pinfunction "2_2") (pintype "passive"))
      (node (ref "U12") (pin "3") (pinfunction "I/O_2_3") (pintype "power_in"))
    )
    (net (code "32") (name "/TC_P_4") (class "Default")
      (node (ref "J9") (pin "1") (pinfunction "+_1") (pintype "passive"))
      (node (ref "R33") (pin "2") (pinfunction "2_2") (pintype "passive"))
      (node (ref "U12") (pin "4") (pinfunction "I/O_3_4") (pintype "power_in"))
    )
    (net (code "33") (name "/TC_P_5") (class "Default")
      (node (ref "J12") (pin "1") (pinfunction "+_1") (pintype "passive"))
      (node (ref "R45") (pin "2") (pinfunction "2_2") (pintype "passive"))
      (node (ref "U16") (pin "3") (pinfunction "I/O_2_3") (pintype "power_in"))
    )
    (net (code "34") (name "/TC_P_6") (class "Default")
      (node (ref "J13") (pin "1") (pinfunction "+_1") (pintype "passive"))
      (node (ref "R47") (pin "2") (pinfunction "2_2") (pintype "passive"))
      (node (ref "U16") (pin "4") (pinfunction "I/O_3_4") (pintype "power_in"))
    )
    (net (code "35") (name "/TC_P_7") (class "Default")
      (node (ref "J16") (pin "1") (pinfunction "+_1") (pintype "passive"))
      (node (ref "R59") (pin "2") (pinfunction "2_2") (pintype "passive"))
      (node (ref "U20") (pin "3") (pinfunction "I/O_2_3") (pintype "power_in"))
    )
    (net (code "36") (name "/TC_P_8") (class "Default")
      (node (ref "J17") (pin "1") (pinfunction "+_1") (pintype "passive"))
      (node (ref "R61") (pin "2") (pinfunction "2_2") (pintype "passive"))
      (node (ref "U20") (pin "4") (pinfunction "I/O_3_4") (pintype "power_in"))
    )
    (net (code "37") (name "/TT_A_1") (class "Default")
      (node (ref "U5") (pin "11") (pinfunction "Alert_1_11") (pintype "passive"))
      (node (ref "U7") (pin "2") (pinfunction "1A_2") (pintype "input"))
    )
    (net (code "38") (name "/TT_A_2") (class "Default")
      (node (ref "U6") (pin "11") (pinfunction "Alert_1_11") (pintype "passive"))
      (node (ref "U7") (pin "9") (pinfunction "2A_9") (pintype "input"))
    )
    (net (code "39") (name "/TT_A_3") (class "Default")
      (node (ref "U11") (pin "2") (pinfunction "1A_2") (pintype "input"))
      (node (ref "U9") (pin "11") (pinfunction "Alert_1_11") (pintype "passive"))
    )
    (net (code "40") (name "/TT_A_4") (class "Default")
      (node (ref "U10") (pin "11") (pinfunction "Alert_1_11") (pintype "passive"))
      (node (ref "U11") (pin "9") (pinfunction "2A_9") (pintype "input"))
    )
    (net (code "41") (name "/TT_A_5") (class "Default")
      (node (ref "U13") (pin "11") (pinfunction "Alert_1_11") (pintype "passive"))
      (node (ref "U15") (pin "2") (pinfunction "1A_2") (pintype "input"))
    )
    (net (code "42") (name "/TT_A_6") (class "Default")
      (node (ref "U14") (pin "11") (pinfunction "Alert_1_11") (pintype "passive"))
      (node (ref "U15") (pin "9") (pinfunction "2A_9") (pintype "input"))
    )
    (net (code "43") (name "/TT_A_7") (class "Default")
      (node (ref "U17") (pin "11") (pinfunction "Alert_1_11") (pintype "passive"))
      (node (ref "U19") (pin "2") (pinfunction "1A_2") (pintype "input"))
    )
    (net (code "44") (name "/TT_A_8") (class "Default")
      (node (ref "U18") (pin "11") (pinfunction "Alert_1_11") (pintype "passive"))
      (node (ref "U19") (pin "9") (pinfunction "2A_9") (pintype "input"))
    )
    (net (code "45") (name "GND") (class "Default")
      (node (ref "C21") (pin "1") (pinfunction "1_1") (pintype "passive"))
      (node (ref "C22") (pin "1") (pinfunction "1_1") (pintype "passive"))
      (node (ref "C23") (pin "1") (pinfunction "1_1") (pintype "passive"))
      (node (ref "C26") (pin "1") (pinfunction "1_1") (pintype "passive"))
      (node (ref "C27") (pin "1") (pinfunction "1_1") (pintype "passive"))
      (node (ref "C28") (pin "1") (pinfunction "1_1") (pintype "passive"))
      (node (ref "C31") (pin "1") (pinfunction "1_1") (pintype "passive"))
      (node (ref "C32") (pin "1") (pinfunction "1_1") (pintype "passive"))
      (node (ref "C33") (pin "1") (pinfunction "1_1") (pintype "passive"))
      (node (ref "C36") (pin "1") (pinfunction "1_1") (pintype "passive"))
      (node (ref "C37") (pin "1") (pinfunction "1_1") (pintype "passive"))
      (node (ref "C38") (pin "1") (pinfunction "1_1") (pintype "passive"))
      (node (ref "D10") (pin "1") (pinfunction "A_1") (pintype "passive"))
      (node (ref "D11") (pin "1") (pinfunction "A_1") (pintype "passive"))
      (node (ref "D4") (pin "1") (pinfunction "A_1") (pintype "passive"))
      (node (ref "D5") (pin "1") (pinfunction "A_1") (pintype "passive"))
      (node (ref "D6") (pin "1") (pinfunction "A_1") (pintype "passive"))
      (node (ref "D7") (pin "1") (pinfunction "A_1") (pintype "passive"))
      (node (ref "D8") (pin "1") (pinfunction "A_1") (pintype "passive"))
      (node (ref "D9") (pin "1") (pinfunction "A_1") (pintype "passive"))
      (node (ref "J10") (pin "2") (pinfunction "-_2") (pintype "passive"))
      (node (ref "J11") (pin "2") (pinfunction "-_2") (pintype "passive"))
      (node (ref "J14") (pin "2") (pinfunction "-_2") (pintype "passive"))
      (node (ref "J15") (pin "2") (pinfunction "-_2") (pintype "passive"))
      (node (ref "J18") (pin "2") (pinfunction "-_2") (pintype "passive"))
      (node (ref "J19") (pin "2") (pinfunction "-_2") (pintype "passive"))
      (node (ref "J6") (pin "2") (pinfunction "-_2") (pintype "passive"))
      (node (ref "J7") (pin "2") (pinfunction "-_2") (pintype "passive"))
      (node (ref "Q12") (pin "3") (pinfunction "S_3") (pintype "passive"))
      (node (ref "Q13") (pin "3") (pinfunction "S_3") (pintype "passive"))
      (node (ref "Q16") (pin "3") (pinfunction "S_3") (pintype "passive"))
      (node (ref "Q17") (pin "3") (pinfunction "S_3") (pintype "passive"))
      (node (ref "Q4") (pin "3") (pinfunction "S_3") (pintype "passive"))
      (node (ref "Q5") (pin "3") (pinfunction "S_3") (pintype "passive"))
      (node (ref "Q8") (pin "3") (pinfunction "S_3") (pintype "passive"))
      (node (ref "Q9") (pin "3") (pinfunction "S_3") (pintype "passive"))
      (node (ref "R27") (pin "1") (pinfunction "1_1") (pintype "passive"))
      (node (ref "R28") (pin "1") (pinfunction "1_1") (pintype "passive"))
      (node (ref "R29") (pin "1") (pinfunction "1_1") (pintype "passive"))
      (node (ref "R30") (pin "1") (pinfunction "1_1") (pintype "passive"))
      (node (ref "R41") (pin "1") (pinfunction "1_1") (pintype "passive"))
      (node (ref "R42") (pin "1") (pinfunction "1_1") (pintype "passive"))
      (node (ref "R43") (pin "1") (pinfunction "1_1") (pintype "passive"))
      (node (ref "R44") (pin "1") (pinfunction "1_1") (pintype "passive"))
      (node (ref "R55") (pin "1") (pinfunction "1_1") (pintype "passive"))
      (node (ref "R56") (pin "1") (pinfunction "1_1") (pintype "passive"))
      (node (ref "R57") (pin "1") (pinfunction "1_1") (pintype "passive"))
      (node (ref "R58") (pin "1") (pinfunction "1_1") (pintype "passive"))
      (node (ref "R69") (pin "1") (pinfunction "1_1") (pintype "passive"))
      (node (ref "R70") (pin "1") (pinfunction "1_1") (pintype "passive"))
      (node (ref "R71") (pin "1") (pinfunction "1_1") (pintype "passive"))
      (node (ref "R72") (pin "1") (pinfunction "1_1") (pintype "passive"))
      (node (ref "U10") (pin "1") (pinfunction "GND_1") (pintype "power_in"))
      (node (ref "U10") (pin "10") (pinfunction "GND_10") (pintype "power_in"))
      (node (ref "U10") (pin "13") (pinfunction "GND_13") (pintype "power_in"))
      (node (ref "U10") (pin "17") (pinfunction "GND_17") (pintype "power_in"))
      (node (ref "U10") (pin "18") (pinfunction "GND_18") (pintype "power_in"))
      (node (ref "U10") (pin "21") (pinfunction "EP_21") (pintype "power_in"))
      (node (ref "U10") (pin "3") (pinfunction "GND_3") (pintype "power_in"))
      (node (ref "U10") (pin "5") (pinfunction "GND_5") (pintype "power_in"))
      (node (ref "U11") (pin "10") (pinfunction "2B_10") (pintype "input"))
      (node (ref "U11") (pin "11") (pinfunction "2C_11") (pintype "input"))
      (node (ref "U11") (pin "3") (pinfunction "1B_3") (pintype "input"))
      (node (ref "U11") (pin "4") (pinfunction "1C_4") (pintype "input"))
      (node (ref "U11") (pin "7") (pinfunction "GND_7") (pintype "power_in"))
      (node (ref "U12") (pin "5") (pinfunction "GND_5") (pintype "power_in"))
      (node (ref "U13") (pin "1") (pinfunction "GND_1") (pintype "power_in"))
      (node (ref "U13") (pin "10") (pinfunction "GND_10") (pintype "power_in"))
      (node (ref "U13") (pin "13") (pinfunction "GND_13") (pintype "power_in"))
      (node (ref "U13") (pin "17") (pinfunction "GND_17") (pintype "power_in"))
      (node (ref "U13") (pin "18") (pinfunction "GND_18") (pintype "power_in"))
      (node (ref "U13") (pin "21") (pinfunction "EP_21") (pintype "power_in"))
      (node (ref "U13") (pin "3") (pinfunction "GND_3") (pintype "power_in"))
      (node (ref "U13") (pin "5") (pinfunction "GND_5") (pintype "power_in"))
      (node (ref "U14") (pin "1") (pinfunction "GND_1") (pintype "power_in"))
      (node (ref "U14") (pin "10") (pinfunction "GND_10") (pintype "power_in"))
      (node (ref "U14") (pin "13") (pinfunction "GND_13") (pintype "power_in"))
      (node (ref "U14") (pin "17") (pinfunction "GND_17") (pintype "power_in"))
      (node (ref "U14") (pin "18") (pinfunction "GND_18") (pintype "power_in"))
      (node (ref "U14") (pin "21") (pinfunction "EP_21") (pintype "power_in"))
      (node (ref "U14") (pin "3") (pinfunction "GND_3") (pintype "power_in"))
      (node (ref "U14") (pin "5") (pinfunction "GND_5") (pintype "power_in"))
      (node (ref "U15") (pin "10") (pinfunction "2B_10") (pintype "input"))
      (node (ref "U15") (pin "11") (pinfunction "2C_11") (pintype "input"))
      (node (ref "U15") (pin "3") (pinfunction "1B_3") (pintype "input"))
      (node (ref "U15") (pin "4") (pinfunction "1C_4") (pintype "input"))
      (node (ref "U15") (pin "7") (pinfunction "GND_7") (pintype "power_in"))
      (node (ref "U16") (pin "5") (pinfunction "GND_5") (pintype "power_in"))
      (node (ref "U17") (pin "1") (pinfunction "GND_1") (pintype "power_in"))
      (node (ref "U17") (pin "10") (pinfunction "GND_10") (pintype "power_in"))
      (node (ref "U17") (pin "13") (pinfunction "GND_13") (pintype "power_in"))
      (node (ref "U17") (pin "17") (pinfunction "GND_17") (pintype "power_in"))
      (node (ref "U17") (pin "18") (pinfunction "GND_18") (pintype "power_in"))
      (node (ref "U17") (pin "21") (pinfunction "EP_21") (pintype "power_in"))
      (node (ref "U17") (pin "3") (pinfunction "GND_3") (pintype "power_in"))
      (node (ref "U17") (pin "5") (pinfunction "GND_5") (pintype "power_in"))
      (node (ref "U18") (pin "1") (pinfunction "GND_1") (pintype "power_in"))
      (node (ref "U18") (pin "10") (pinfunction "GND_10") (pintype "power_in"))
      (node (ref "U18") (pin "13") (pinfunction "GND_13") (pintype "power_in"))
      (node (ref "U18") (pin "17") (pinfunction "GND_17") (pintype "power_in"))
      (node (ref "U18") (pin "18") (pinfunction "GND_18") (pintype "power_in"))
      (node (ref "U18") (pin "21") (pinfunction "EP_21") (pintype "power_in"))
      (node (ref "U18") (pin "3") (pinfunction "GND_3") (pintype "power_in"))
      (node (ref "U18") (pin "5") (pinfunction "GND_5") (pintype "power_in"))
      (node (ref "U19") (pin "10") (pinfunction "2B_10") (pintype "input"))
      (node (ref "U19") (pin "11") (pinfunction "2C_11") (pintype "input"))
      (node (ref "U19") (pin "3") (pinfunction "1B_3") (pintype "input"))
      (node (ref "U19") (pin "4") (pinfunction "1C_4") (pintype "input"))
      (node (ref "U19") (pin "7") (pinfunction "GND_7") (pintype "power_in"))
      (node (ref "U20") (pin "5") (pinfunction "GND_5") (pintype "power_in"))
      (node (ref "U5") (pin "1") (pinfunction "GND_1") (pintype "power_in"))
      (node (ref "U5") (pin "10") (pinfunction "GND_10") (pintype "power_in"))
      (node (ref "U5") (pin "13") (pinfunction "GND_13") (pintype "power_in"))
      (node (ref "U5") (pin "17") (pinfunction "GND_17") (pintype "power_in"))
      (node (ref "U5") (pin "18") (pinfunction "GND_18") (pintype "power_in"))
      (node (ref "U5") (pin "21") (pinfunction "EP_21") (pintype "power_in"))
      (node (ref "U5") (pin "3") (pinfunction "GND_3") (pintype "power_in"))
      (node (ref "U5") (pin "5") (pinfunction "GND_5") (pintype "power_in"))
      (node (ref "U6") (pin "1") (pinfunction "GND_1") (pintype "power_in"))
      (node (ref "U6") (pin "10") (pinfunction "GND_10") (pintype "power_in"))
      (node (ref "U6") (pin "13") (pinfunction "GND_13") (pintype "power_in"))
      (node (ref "U6") (pin "17") (pinfunction "GND_17") (pintype "power_in"))
      (node (ref "U6") (pin "18") (pinfunction "GND_18") (pintype "power_in"))
      (node (ref "U6") (pin "21") (pinfunction "EP_21") (pintype "power_in"))
      (node (ref "U6") (pin "3") (pinfunction "GND_3") (pintype "power_in"))
      (node (ref "U6") (pin "5") (pinfunction "GND_5") (pintype "power_in"))
      (node (ref "U7") (pin "10") (pinfunction "2B_10") (pintype "input"))
      (node (ref "U7") (pin "11") (pinfunction "2C_11") (pintype "input"))
      (node (ref "U7") (pin "3") (pinfunction "1B_3") (pintype "input"))
      (node (ref "U7") (pin "4") (pinfunction "1C_4") (pintype "input"))
      (node (ref "U7") (pin "7") (pinfunction "GND_7") (pintype "power_in"))
      (node (ref "U8") (pin "5") (pinfunction "GND_5") (pintype "power_in"))
      (node (ref "U9") (pin "1") (pinfunction "GND_1") (pintype "power_in"))
      (node (ref "U9") (pin "10") (pinfunction "GND_10") (pintype "power_in"))
      (node (ref "U9") (pin "13") (pinfunction "GND_13") (pintype "power_in"))
      (node (ref "U9") (pin "17") (pinfunction "GND_17") (pintype "power_in"))
      (node (ref "U9") (pin "18") (pinfunction "GND_18") (pintype "power_in"))
      (node (ref "U9") (pin "21") (pinfunction "EP_21") (pintype "power_in"))
      (node (ref "U9") (pin "3") (pinfunction "GND_3") (pintype "power_in"))
      (node (ref "U9") (pin "5") (pinfunction "GND_5") (pintype "power_in"))
    )
    (net (code "46") (name "Net-(D4-K)") (class "Default")
      (node (ref "D4") (pin "2") (pinfunction "K_2") (pintype "passive"))
      (node (ref "J6") (pin "1") (pinfunction "+_1") (pintype "passive"))
      (node (ref "Q2") (pin "D") (pinfunction "D_D") (pintype "passive"))
    )
    (net (code "47") (name "Net-(D5-K)") (class "Default")
      (node (ref "D5") (pin "2") (pinfunction "K_2") (pintype "passive"))
      (node (ref "J7") (pin "1") (pinfunction "+_1") (pintype "passive"))
      (node (ref "Q3") (pin "D") (pinfunction "D_D") (pintype "passive"))
    )
    (net (code "48") (name "Net-(D6-K)") (class "Default")
      (node (ref "D6") (pin "2") (pinfunction "K_2") (pintype "passive"))
      (node (ref "J10") (pin "1") (pinfunction "+_1") (pintype "passive"))
      (node (ref "Q6") (pin "D") (pinfunction "D_D") (pintype "passive"))
    )
    (net (code "49") (name "Net-(D7-K)") (class "Default")
      (node (ref "D7") (pin "2") (pinfunction "K_2") (pintype "passive"))
      (node (ref "J11") (pin "1") (pinfunction "+_1") (pintype "passive"))
      (node (ref "Q7") (pin "D") (pinfunction "D_D") (pintype "passive"))
    )
    (net (code "50") (name "Net-(D8-K)") (class "Default")
      (node (ref "D8") (pin "2") (pinfunction "K_2") (pintype "passive"))
      (node (ref "J14") (pin "1") (pinfunction "+_1") (pintype "passive"))
      (node (ref "Q10") (pin "D") (pinfunction "D_D") (pintype "passive"))
    )
    (net (code "51") (name "Net-(D9-K)") (class "Default")
      (node (ref "D9") (pin "2") (pinfunction "K_2") (pintype "passive"))
      (node (ref "J15") (pin "1") (pinfunction "+_1") (pintype "passive"))
      (node (ref "Q11") (pin "D") (pinfunction "D_D") (pintype "passive"))
    )
    (net (code "52") (name "Net-(D10-K)") (class "Default")
      (node (ref "D10") (pin "2") (pinfunction "K_2") (pintype "passive"))
      (node (ref "J18") (pin "1") (pinfunction "+_1") (pintype "passive"))
      (node (ref "Q14") (pin "D") (pinfunction "D_D") (pintype "passive"))
    )
    (net (code "53") (name "Net-(D11-K)") (class "Default")
      (node (ref "D11") (pin "2") (pinfunction "K_2") (pintype "passive"))
      (node (ref "J19") (pin "1") (pinfunction "+_1") (pintype "passive"))
      (node (ref "Q15") (pin "D") (pinfunction "D_D") (pintype "passive"))
    )
    (net (code "54") (name "Net-(Q2-PadG)") (class "Default")
      (node (ref "Q2") (pin "G") (pinfunction "G_G") (pintype "passive"))
      (node (ref "R18") (pin "2") (pinfunction "2_2") (pintype "passive"))
      (node (ref "R23") (pin "2") (pinfunction "2_2") (pintype "passive"))
    )
    (net (code "55") (name "Net-(Q3-PadG)") (class "Default")
      (node (ref "Q3") (pin "G") (pinfunction "G_G") (pintype "passive"))
      (node (ref "R20") (pin "2") (pinfunction "2_2") (pintype "passive"))
      (node (ref "R24") (pin "2") (pinfunction "2_2") (pintype "passive"))
    )
    (net (code "56") (name "Net-(Q4-D)") (class "Default")
      (node (ref "Q4") (pin "2") (pinfunction "D_2") (pintype "passive"))
      (node (ref "R23") (pin "1") (pinfunction "1_1") (pintype "passive"))
    )
    (net (code "57") (name "Net-(Q5-D)") (class "Default")
      (node (ref "Q5") (pin "2") (pinfunction "D_2") (pintype "passive"))
      (node (ref "R24") (pin "1") (pinfunction "1_1") (pintype "passive"))
    )
    (net (code "58") (name "Net-(Q6-PadG)") (class "Default")
      (node (ref "Q6") (pin "G") (pinfunction "G_G") (pintype "passive"))
      (node (ref "R32") (pin "2") (pinfunction "2_2") (pintype "passive"))
      (node (ref "R37") (pin "2") (pinfunction "2_2") (pintype "passive"))
    )
    (net (code "59") (name "Net-(Q7-PadG)") (class "Default")
      (node (ref "Q7") (pin "G") (pinfunction "G_G") (pintype "passive"))
      (node (ref "R34") (pin "2") (pinfunction "2_2") (pintype "passive"))
      (node (ref "R38") (pin "2") (pinfunction "2_2") (pintype "passive"))
    )
    (net (code "60") (name "Net-(Q8-D)") (class "Default")
      (node (ref "Q8") (pin "2") (pinfunction "D_2") (pintype "passive"))
      (node (ref "R37") (pin "1") (pinfunction "1_1") (pintype "passive"))
    )
    (net (code "61") (name "Net-(Q9-D)") (class "Default")
      (node (ref "Q9") (pin "2") (pinfunction "D_2") (pintype "passive"))
      (node (ref "R38") (pin "1") (pinfunction "1_1") (pintype "passive"))
    )
    (net (code "62") (name "Net-(Q10-PadG)") (class "Default")
      (node (ref "Q10") (pin "G") (pinfunction "G_G") (pintype "passive"))
      (node (ref "R46") (pin "2") (pinfunction "2_2") (pintype "passive"))
      (node (ref "R51") (pin "2") (pinfunction "2_2") (pintype "passive"))
    )
    (net (code "63") (name "Net-(Q11-PadG)") (class "Default")
      (node (ref "Q11") (pin "G") (pinfunction "G_G") (pintype "passive"))
      (node (ref "R48") (pin "2") (pinfunction "2_2") (pintype "passive"))
      (node (ref "R52") (pin "2") (pinfunction "2_2") (pintype "passive"))
    )
    (net (code "64") (name "Net-(Q12-D)") (class "Default")
      (node (ref "Q12") (pin "2") (pinfunction "D_2") (pintype "passive"))
      (node (ref "R51") (pin "1") (pinfunction "1_1") (pintype "passive"))
    )
    (net (code "65") (name "Net-(Q13-D)") (class "Default")
      (node (ref "Q13") (pin "2") (pinfunction "D_2") (pintype "passive"))
      (node (ref "R52") (pin "1") (pinfunction "1_1") (pintype "passive"))
    )
    (net (code "66") (name "Net-(Q14-PadG)") (class "Default")
      (node (ref "Q14") (pin "G") (pinfunction "G_G") (pintype "passive"))
      (node (ref "R60") (pin "2") (pinfunction "2_2") (pintype "passive"))
      (node (ref "R65") (pin "2") (pinfunction "2_2") (pintype "passive"))
    )
    (net (code "67") (name "Net-(Q15-PadG)") (class "Default")
      (node (ref "Q15") (pin "G") (pinfunction "G_G") (pintype "passive"))
      (node (ref "R62") (pin "2") (pinfunction "2_2") (pintype "passive"))
      (node (ref "R66") (pin "2") (pinfunction "2_2") (pintype "passive"))
    )
    (net (code "68") (name "Net-(Q16-D)") (class "Default")
      (node (ref "Q16") (pin "2") (pinfunction "D_2") (pintype "passive"))
      (node (ref "R65") (pin "1") (pinfunction "1_1") (pintype "passive"))
    )
    (net (code "69") (name "Net-(Q17-D)") (class "Default")
      (node (ref "Q17") (pin "2") (pinfunction "D_2") (pintype "passive"))
      (node (ref "R66") (pin "1") (pinfunction "1_1") (pintype "passive"))
    )
    (net (code "70") (name "Net-(U5-ADDR)") (class "Default")
      (node (ref "R25") (pin "2") (pinfunction "2_2") (pintype "passive"))
      (node (ref "R27") (pin "2") (pinfunction "2_2") (pintype "passive"))
      (node (ref "U5") (pin "16") (pinfunction "ADDR_16") (pintype "input"))
    )
    (net (code "71") (name "Net-(U5-VIN+)") (class "Default")
      (node (ref "C19") (pin "2") (pinfunction "2_2") (pintype "passive"))
      (node (ref "R17") (pin "1") (pinfunction "1_1") (pintype "passive"))
      (node (ref "U5") (pin "2") (pinfunction "VIN+_2") (pintype "power_in"))
    )
    (net (code "72") (name "Net-(U5-VIN-)") (class "Default")
      (node (ref "C19") (pin "1") (pinfunction "1_1") (pintype "passive"))
      (node (ref "R21") (pin "1") (pinfunction "1_1") (pintype "passive"))
      (node (ref "U5") (pin "4") (pinfunction "VIN-_4") (pintype "power_in"))
    )
    (net (code "73") (name "Net-(U6-ADDR)") (class "Default")
      (node (ref "R26") (pin "2") (pinfunction "2_2") (pintype "passive"))
      (node (ref "R29") (pin "2") (pinfunction "2_2") (pintype "passive"))
      (node (ref "U6") (pin "16") (pinfunction "ADDR_16") (pintype "input"))
    )
    (net (code "74") (name "Net-(U6-VIN+)") (class "Default")
      (node (ref "C20") (pin "2") (pinfunction "2_2") (pintype "passive"))
      (node (ref "R19") (pin "1") (pinfunction "1_1") (pintype "passive"))
      (node (ref "U6") (pin "2") (pinfunction "VIN+_2") (pintype "power_in"))
    )
    (net (code "75") (name "Net-(U6-VIN-)") (class "Default")
      (node (ref "C20") (pin "1") (pinfunction "1_1") (pintype "passive"))
      (node (ref "R22") (pin "1") (pinfunction "1_1") (pintype "passive"))
      (node (ref "U6") (pin "4") (pinfunction "VIN-_4") (pintype "power_in"))
    )
    (net (code "76") (name "Net-(U9-ADDR)") (class "Default")
      (node (ref "R39") (pin "2") (pinfunction "2_2") (pintype "passive"))
      (node (ref "R41") (pin "2") (pinfunction "2_2") (pintype "passive"))
      (node (ref "U9") (pin "16") (pinfunction "ADDR_16") (pintype "input"))
    )
    (net (code "77") (name "Net-(U9-VIN+)") (class "Default")
      (node (ref "C24") (pin "2") (pinfunction "2_2") (pintype "passive"))
      (node (ref "R31") (pin "1") (pinfunction "1_1") (pintype "passive"))
      (node (ref "U9") (pin "2") (pinfunction "VIN+_2") (pintype "power_in"))
    )
    (net (code "78") (name "Net-(U9-VIN-)") (class "Default")
      (node (ref "C24") (pin "1") (pinfunction "1_1") (pintype "passive"))
      (node (ref "R35") (pin "1") (pinfunction "1_1") (pintype "passive"))
      (node (ref "U9") (pin "4") (pinfunction "VIN-_4") (pintype "power_in"))
    )
    (net (code "79") (name "Net-(U10-ADDR)") (class "Default")
      (node (ref "R40") (pin "2") (pinfunction "2_2") (pintype "passive"))
      (node (ref "R43") (pin "2") (pinfunction "2_2") (pintype "passive"))
      (node (ref "U10") (pin "16") (pinfunction "ADDR_16") (pintype "input"))
    )
    (net (code "80") (name "Net-(U10-VIN+)") (class "Default")
      (node (ref "C25") (pin "2") (pinfunction "2_2") (pintype "passive"))
      (node (ref "R33") (pin "1") (pinfunction "1_1") (pintype "passive"))
      (node (ref "U10") (pin "2") (pinfunction "VIN+_2") (pintype "power_in"))
    )
    (net (code "81") (name "Net-(U10-VIN-)") (class "Default")
      (node (ref "C25") (pin "1") (pinfunction "1_1") (pintype "passive"))
      (node (ref "R36") (pin "1") (pinfunction "1_1") (pintype "passive"))
      (node (ref "U10") (pin "4") (pinfunction "VIN-_4") (pintype "power_in"))
    )
    (net (code "82") (name "Net-(U13-ADDR)") (class "Default")
      (node (ref "R53") (pin "2") (pinfunction "2_2") (pintype "passive"))
      (node (ref "R55") (pin "2") (pinfunction "2_2") (pintype "passive"))
      (node (ref "U13") (pin "16") (pinfunction "ADDR_16") (pintype "input"))
    )
    (net (code "83") (name "Net-(U13-VIN+)") (class "Default")
      (node (ref "C29") (pin "2") (pinfunction "2_2") (pintype "passive"))
      (node (ref "R45") (pin "1") (pinfunction "1_1") (pintype "passive"))
      (node (ref "U13") (pin "2") (pinfunction "VIN+_2") (pintype "power_in"))
    )
    (net (code "84") (name "Net-(U13-VIN-)") (class "Default")
      (node (ref "C29") (pin "1") (pinfunction "1_1") (pintype "passive"))
      (node (ref "R49") (pin "1") (pinfunction "1_1") (pintype "passive"))
      (node (ref "U13") (pin "4") (pinfunction "VIN-_4") (pintype "power_in"))
    )
    (net (code "85") (name "Net-(U14-ADDR)") (class "Default")
      (node (ref "R54") (pin "2") (pinfunction "2_2") (pintype "passive"))
      (node (ref "R57") (pin "2") (pinfunction "2_2") (pintype "passive"))
      (node (ref "U14") (pin "16") (pinfunction "ADDR_16") (pintype "input"))
    )
    (net (code "86") (name "Net-(U14-VIN+)") (class "Default")
      (node (ref "C30") (pin "2") (pinfunction "2_2") (pintype "passive"))
      (node (ref "R47") (pin "1") (pinfunction "1_1") (pintype "passive"))
      (node (ref "U14") (pin "2") (pinfunction "VIN+_2") (pintype "power_in"))
    )
    (net (code "87") (name "Net-(U14-VIN-)") (class "Default")
      (node (ref "C30") (pin "1") (pinfunction "1_1") (pintype "passive"))
      (node (ref "R50") (pin "1") (pinfunction "1_1") (pintype "passive"))
      (node (ref "U14") (pin "4") (pinfunction "VIN-_4") (pintype "power_in"))
    )
    (net (code "88") (name "Net-(U17-ADDR)") (class "Default")
      (node (ref "R67") (pin "2") (pinfunction "2_2") (pintype "passive"))
      (node (ref "R69") (pin "2") (pinfunction "2_2") (pintype "passive"))
      (node (ref "U17") (pin "16") (pinfunction "ADDR_16") (pintype "input"))
    )
    (net (code "89") (name "Net-(U17-VIN+)") (class "Default")
      (node (ref "C34") (pin "2") (pinfunction "2_2") (pintype "passive"))
      (node (ref "R59") (pin "1") (pinfunction "1_1") (pintype "passive"))
      (node (ref "U17") (pin "2") (pinfunction "VIN+_2") (pintype "power_in"))
    )
    (net (code "90") (name "Net-(U17-VIN-)") (class "Default")
      (node (ref "C34") (pin "1") (pinfunction "1_1") (pintype "passive"))
      (node (ref "R63") (pin "1") (pinfunction "1_1") (pintype "passive"))
      (node (ref "U17") (pin "4") (pinfunction "VIN-_4") (pintype "power_in"))
    )
    (net (code "91") (name "Net-(U18-ADDR)") (class "Default")
      (node (ref "R68") (pin "2") (pinfunction "2_2") (pintype "passive"))
      (node (ref "R71") (pin "2") (pinfunction "2_2") (pintype "passive"))
      (node (ref "U18") (pin "16") (pinfunction "ADDR_16") (pintype "input"))
    )
    (net (code "92") (name "Net-(U18-VIN+)") (class "Default")
      (node (ref "C35") (pin "2") (pinfunction "2_2") (pintype "passive"))
      (node (ref "R61") (pin "1") (pinfunction "1_1") (pintype "passive"))
      (node (ref "U18") (pin "2") (pinfunction "VIN+_2") (pintype "power_in"))
    )
    (net (code "93") (name "Net-(U18-VIN-)") (class "Default")
      (node (ref "C35") (pin "1") (pinfunction "1_1") (pintype "passive"))
      (node (ref "R64") (pin "1") (pinfunction "1_1") (pintype "passive"))
      (node (ref "U18") (pin "4") (pinfunction "VIN-_4") (pintype "power_in"))
    )
    (net (code "94") (name "unconnected-(U5-Alert_2-Pad12)") (class "Default")
      (node (ref "U5") (pin "12") (pinfunction "Alert_2_12") (pintype "passive"))
    )
    (net (code "95") (name "unconnected-(U5-Alert_3-Pad14)") (class "Default")
      (node (ref "U5") (pin "14") (pinfunction "Alert_3_14") (pintype "passive"))
    )
    (net (code "96") (name "unconnected-(U5-Alert_4-Pad15)") (class "Default")
      (node (ref "U5") (pin "15") (pinfunction "Alert_4_15") (pintype "passive"))
    )
    (net (code "97") (name "unconnected-(U5-OC_Alert-Pad9)") (class "Default")
      (node (ref "U5") (pin "9") (pinfunction "OC_Alert_9") (pintype "passive"))
    )
    (net (code "98") (name "unconnected-(U5-SC_Alert-Pad7)") (class "Default")
      (node (ref "U5") (pin "7") (pinfunction "SC_Alert_7") (pintype "passive"))
    )
    (net (code "99") (name "unconnected-(U5-VSENSE-Pad6)") (class "Default")
      (node (ref "U5") (pin "6") (pinfunction "VSENSE_6") (pintype "passive"))
    )
    (net (code "100") (name "unconnected-(U6-Alert_2-Pad12)") (class "Default")
      (node (ref "U6") (pin "12") (pinfunction "Alert_2_12") (pintype "passive"))
    )
    (net (code "101") (name "unconnected-(U6-Alert_3-Pad14)") (class "Default")
      (node (ref "U6") (pin "14") (pinfunction "Alert_3_14") (pintype "passive"))
    )
    (net (code "102") (name "unconnected-(U6-Alert_4-Pad15)") (class "Default")
      (node (ref "U6") (pin "15") (pinfunction "Alert_4_15") (pintype "passive"))
    )
    (net (code "103") (name "unconnected-(U6-OC_Alert-Pad9)") (class "Default")
      (node (ref "U6") (pin "9") (pinfunction "OC_Alert_9") (pintype "passive"))
    )
    (net (code "104") (name "unconnected-(U6-SC_Alert-Pad7)") (class "Default")
      (node (ref "U6") (pin "7") (pinfunction "SC_Alert_7") (pintype "passive"))
    )
    (net (code "105") (name "unconnected-(U6-VSENSE-Pad6)") (class "Default")
      (node (ref "U6") (pin "6") (pinfunction "VSENSE_6") (pintype "passive"))
    )
    (net (code "106") (name "unconnected-(U7C-NC-Pad6)") (class "Default")
      (node (ref "U7") (pin "6") (pinfunction "NC_6") (pintype "passive"))
    )
    (net (code "107") (name "unconnected-(U7C-NC-Pad8)") (class "Default")
      (node (ref "U7") (pin "8") (pinfunction "NC_8") (pintype "passive"))
    )
    (net (code "108") (name "unconnected-(U9-Alert_2-Pad12)") (class "Default")
      (node (ref "U9") (pin "12") (pinfunction "Alert_2_12") (pintype "passive"))
    )
    (net (code "109") (name "unconnected-(U9-Alert_3-Pad14)") (class "Default")
      (node (ref "U9") (pin "14") (pinfunction "Alert_3_14") (pintype "passive"))
    )
    (net (code "110") (name "unconnected-(U9-Alert_4-Pad15)") (class "Default")
      (node (ref "U9") (pin "15") (pinfunction "Alert_4_15") (pintype "passive"))
    )
    (net (code "111") (name "unconnected-(U9-OC_Alert-Pad9)") (class "Default")
      (node (ref "U9") (pin "9") (pinfunction "OC_Alert_9") (pintype "passive"))
    )
    (net (code "112") (name "unconnected-(U9-SC_Alert-Pad7)") (class "Default")
      (node (ref "U9") (pin "7") (pinfunction "SC_Alert_7") (pintype "passive"))
    )
    (net (code "113") (name "unconnected-(U9-VSENSE-Pad6)") (class "Default")
      (node (ref "U9") (pin "6") (pinfunction "VSENSE_6") (pintype "passive"))
    )
    (net (code "114") (name "unconnected-(U10-Alert_2-Pad12)") (class "Default")
      (node (ref "U10") (pin "12") (pinfunction "Alert_2_12") (pintype "passive"))
    )
    (net (code "115") (name "unconnected-(U10-Alert_3-Pad14)") (class "Default")
      (node (ref "U10") (pin "14") (pinfunction "Alert_3_14") (pintype "passive"))
    )
    (net (code "116") (name "unconnected-(U10-Alert_4-Pad15)") (class "Default")
      (node (ref "U10") (pin "15") (pinfunction "Alert_4_15") (pintype "passive"))
    )
    (net (code "117") (name "unconnected-(U10-OC_Alert-Pad9)") (class "Default")
      (node (ref "U10") (pin "9") (pinfunction "OC_Alert_9") (pintype "passive"))
    )
    (net (code "118") (name "unconnected-(U10-SC_Alert-Pad7)") (class "Default")
      (node (ref "U10") (pin "7") (pinfunction "SC_Alert_7") (pintype "passive"))
    )
    (net (code "119") (name "unconnected-(U10-VSENSE-Pad6)") (class "Default")
      (node (ref "U10") (pin "6") (pinfunction "VSENSE_6") (pintype "passive"))
    )
    (net (code "120") (name "unconnected-(U11C-NC-Pad6)") (class "Default")
      (node (ref "U11") (pin "6") (pinfunction "NC_6") (pintype "passive"))
    )
    (net (code "121") (name "unconnected-(U11C-NC-Pad8)") (class "Default")
      (node (ref "U11") (pin "8") (pinfunction "NC_8") (pintype "passive"))
    )
    (net (code "122") (name "unconnected-(U13-Alert_2-Pad12)") (class "Default")
      (node (ref "U13") (pin "12") (pinfunction "Alert_2_12") (pintype "passive"))
    )
    (net (code "123") (name "unconnected-(U13-Alert_3-Pad14)") (class "Default")
      (node (ref "U13") (pin "14") (pinfunction "Alert_3_14") (pintype "passive"))
    )
    (net (code "124") (name "unconnected-(U13-Alert_4-Pad15)") (class "Default")
      (node (ref "U13") (pin "15") (pinfunction "Alert_4_15") (pintype "passive"))
    )
    (net (code "125") (name "unconnected-(U13-OC_Alert-Pad9)") (class "Default")
      (node (ref "U13") (pin "9") (pinfunction "OC_Alert_9") (pintype "passive"))
    )
    (net (code "126") (name "unconnected-(U13-SC_Alert-Pad7)") (class "Default")
      (node (ref "U13") (pin "7") (pinfunction "SC_Alert_7") (pintype "passive"))
    )
    (net (code "127") (name "unconnected-(U13-VSENSE-Pad6)") (class "Default")
      (node (ref "U13") (pin "6") (pinfunction "VSENSE_6") (pintype "passive"))
    )
    (net (code "128") (name "unconnected-(U14-Alert_2-Pad12)") (class "Default")
      (node (ref "U14") (pin "12") (pinfunction "Alert_2_12") (pintype "passive"))
    )
    (net (code "129") (name "unconnected-(U14-Alert_3-Pad14)") (class "Default")
      (node (ref "U14") (pin "14") (pinfunction "Alert_3_14") (pintype "passive"))
    )
    (net (code "130") (name "unconnected-(U14-Alert_4-Pad15)") (class "Default")
      (node (ref "U14") (pin "15") (pinfunction "Alert_4_15") (pintype "passive"))
    )
    (net (code "131") (name "unconnected-(U14-OC_Alert-Pad9)") (class "Default")
      (node (ref "U14") (pin "9") (pinfunction "OC_Alert_9") (pintype "passive"))
    )
    (net (code "132") (name "unconnected-(U14-SC_Alert-Pad7)") (class "Default")
      (node (ref "U14") (pin "7") (pinfunction "SC_Alert_7") (pintype "passive"))
    )
    (net (code "133") (name "unconnected-(U14-VSENSE-Pad6)") (class "Default")
      (node (ref "U14") (pin "6") (pinfunction "VSENSE_6") (pintype "passive"))
    )
    (net (code "134") (name "unconnected-(U15C-NC-Pad6)") (class "Default")
      (node (ref "U15") (pin "6") (pinfunction "NC_6") (pintype "passive"))
    )
    (net (code "135") (name "unconnected-(U15C-NC-Pad8)") (class "Default")
      (node (ref "U15") (pin "8") (pinfunction "NC_8") (pintype "passive"))
    )
    (net (code "136") (name "unconnected-(U17-Alert_2-Pad12)") (class "Default")
      (node (ref "U17") (pin "12") (pinfunction "Alert_2_12") (pintype "passive"))
    )
    (net (code "137") (name "unconnected-(U17-Alert_3-Pad14)") (class "Default")
      (node (ref "U17") (pin "14") (pinfunction "Alert_3_14") (pintype "passive"))
    )
    (net (code "138") (name "unconnected-(U17-Alert_4-Pad15)") (class "Default")
      (node (ref "U17") (pin "15") (pinfunction "Alert_4_15") (pintype "passive"))
    )
    (net (code "139") (name "unconnected-(U17-OC_Alert-Pad9)") (class "Default")
      (node (ref "U17") (pin "9") (pinfunction "OC_Alert_9") (pintype "passive"))
    )
    (net (code "140") (name "unconnected-(U17-SC_Alert-Pad7)") (class "Default")
      (node (ref "U17") (pin "7") (pinfunction "SC_Alert_7") (pintype "passive"))
    )
    (net (code "141") (name "unconnected-(U17-VSENSE-Pad6)") (class "Default")
      (node (ref "U17") (pin "6") (pinfunction "VSENSE_6") (pintype "passive"))
    )
    (net (code "142") (name "unconnected-(U18-Alert_2-Pad12)") (class "Default")
      (node (ref "U18") (pin "12") (pinfunction "Alert_2_12") (pintype "passive"))
    )
    (net (code "143") (name "unconnected-(U18-Alert_3-Pad14)") (class "Default")
      (node (ref "U18") (pin "14") (pinfunction "Alert_3_14") (pintype "passive"))
    )
    (net (code "144") (name "unconnected-(U18-Alert_4-Pad15)") (class "Default")
      (node (ref "U18") (pin "15") (pinfunction "Alert_4_15") (pintype "passive"))
    )
    (net (code "145") (name "unconnected-(U18-OC_Alert-Pad9)") (class "Default")
      (node (ref "U18") (pin "9") (pinfunction "OC_Alert_9") (pintype "passive"))
    )
    (net (code "146") (name "unconnected-(U18-SC_Alert-Pad7)") (class "Default")
      (node (ref "U18") (pin "7") (pinfunction "SC_Alert_7") (pintype "passive"))
    )
    (net (code "147") (name "unconnected-(U18-VSENSE-Pad6)") (class "Default")
      (node (ref "U18") (pin "6") (pinfunction "VSENSE_6") (pintype "passive"))
    )
    (net (code "148") (name "unconnected-(U19C-NC-Pad6)") (class "Default")
      (node (ref "U19") (pin "6") (pinfunction "NC_6") (pintype "passive"))
    )
    (net (code "149") (name "unconnected-(U19C-NC-Pad8)") (class "Default")
      (node (ref "U19") (pin "8") (pinfunction "NC_8") (pintype "passive"))
    )
  )
)
